# ProPrj___2025-10-14.net
KiCad netlist of a schematic drawn in EasyEDA Pro
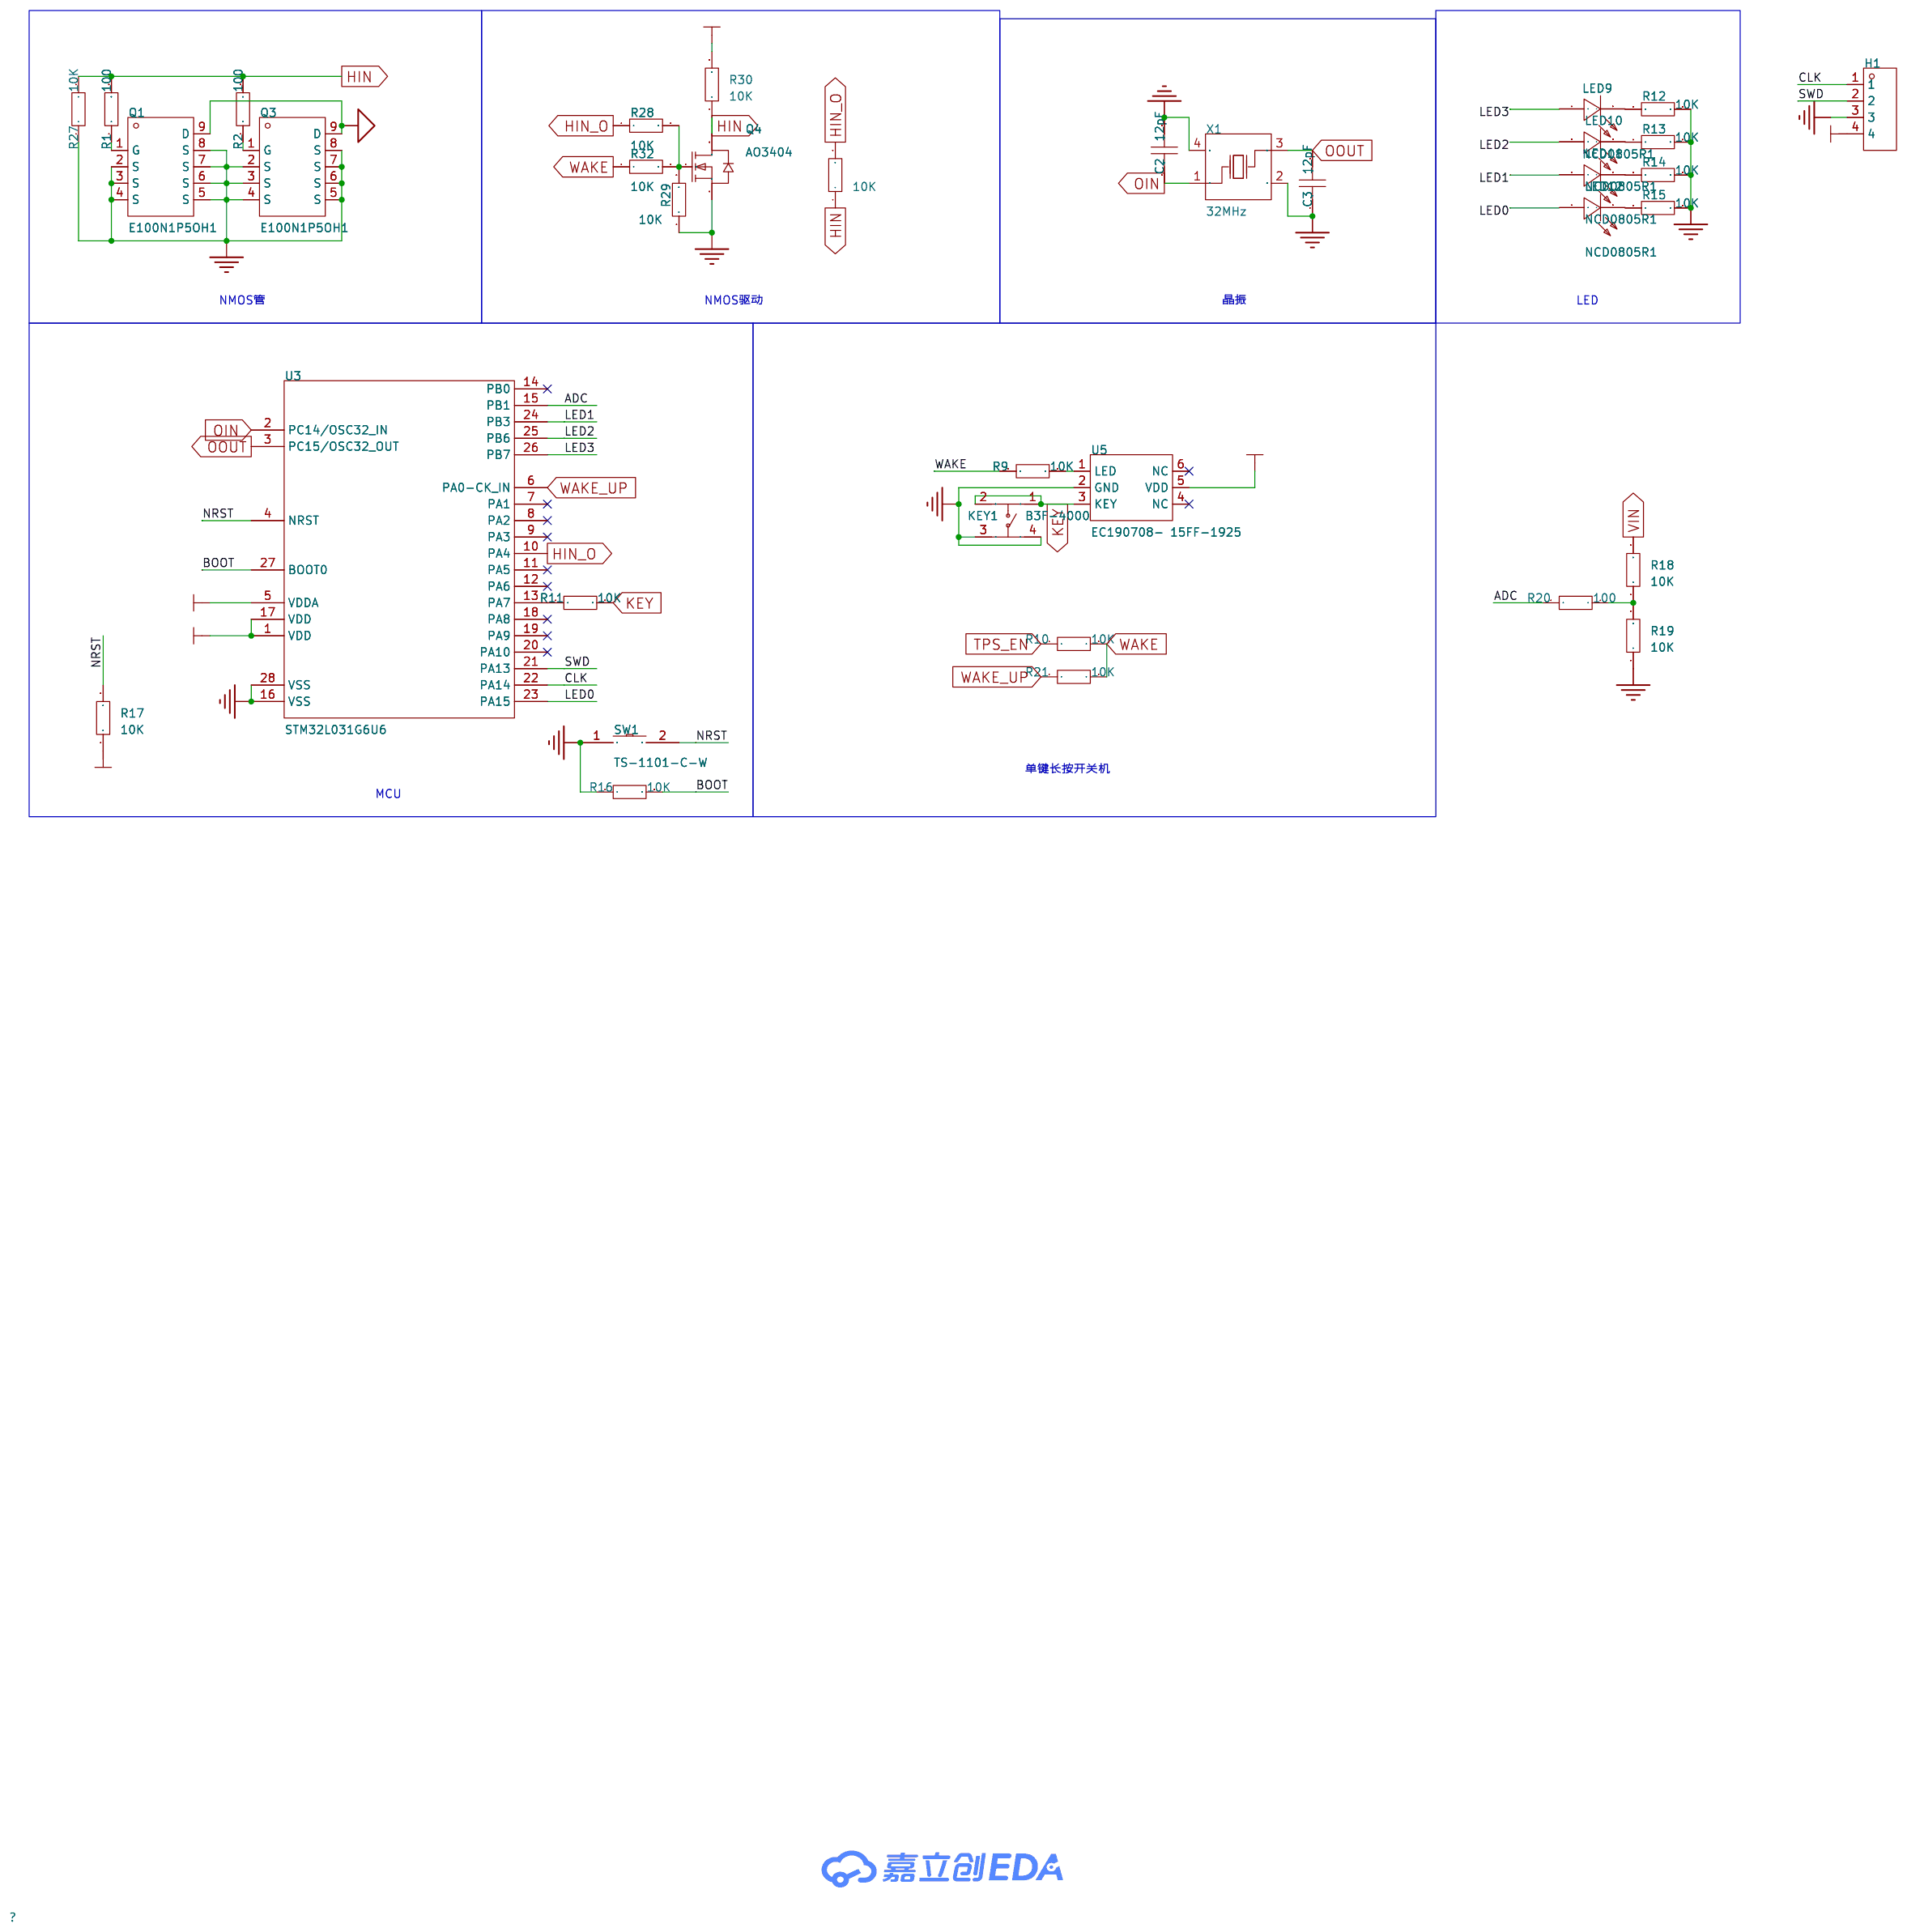
[diagram p0: P1]
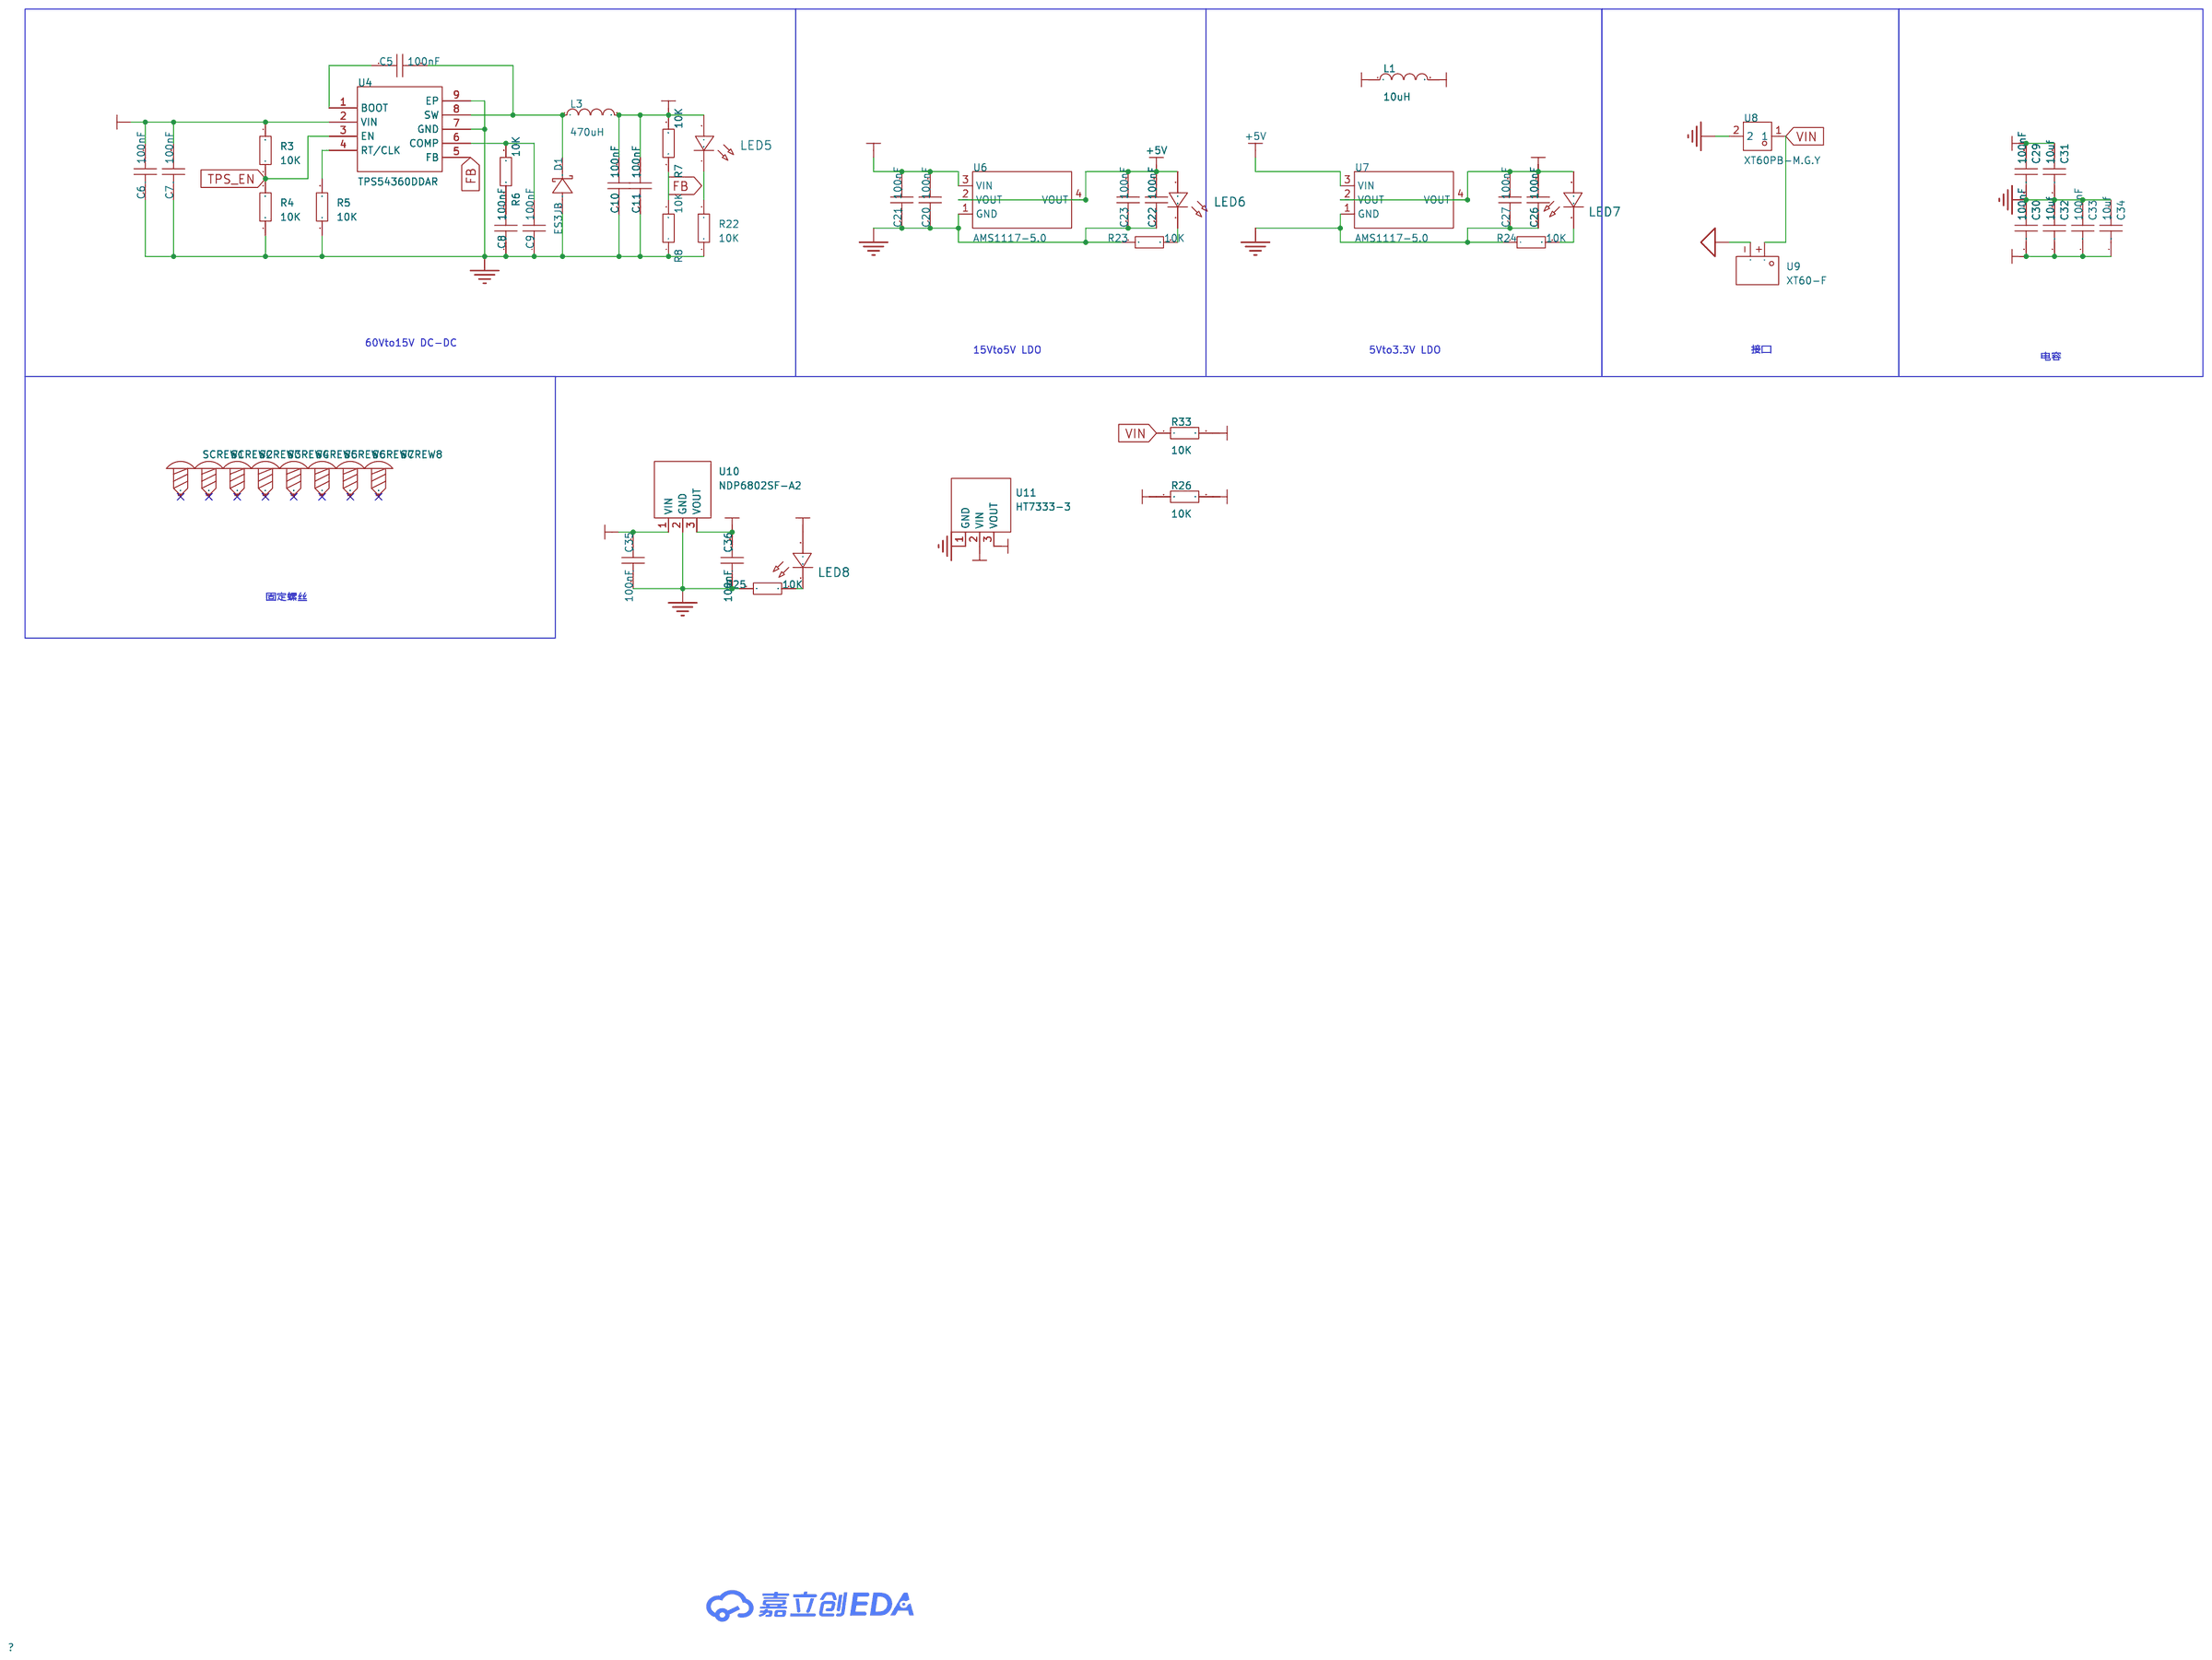
[diagram p1: PWOER]

(export (version "E")
  (design (tool "Eeschema 10.0.6"))
  (components
    (comp (ref "C2")
      (value "12pF")
      (footprint "easyedapro:C1206")
      (libsource (lib "easyedapro") (part "CapAcitance"))
    )
    (comp (ref "C3")
      (value "12pF")
      (footprint "easyedapro:C1206")
      (libsource (lib "easyedapro") (part "CapAcitance"))
    )
    (comp (ref "H1")
      (value "~")
      (footprint "easyedapro:HDR-TH_4P-P2.54-V-F")
      (libsource (lib "easyedapro") (part "2.54-1*4P母"))
    )
    (comp (ref "KEY1")
      (value "B3F-4000")
      (footprint "easyedapro:KEY-TH_4P-L12.0-W12.0-P5.00-LS13.4-EH")
      (description "电路结构:单刀单掷;按钮形状:圆形按钮;安装方式:直插;开关长度:12mm;开关宽度:12mm;开关高度:4.3mm;触点电流:50mA;额定电压(DC):24V;带灯:-;机械寿命:-;")
      (fields (field (name "Manufacturer") "OMRON(欧姆龙)"))
      (libsource (lib "easyedapro") (part "B3F-4000"))
    )
    (comp (ref "LED9")
      (value "NCD0805R1")
      (footprint "easyedapro:LED0805-R-RD")
      (fields (field (name "Manufacturer") "国星光电"))
      (libsource (lib "easyedapro") (part "FC-2012HRK-620D"))
    )
    (comp (ref "LED10")
      (value "NCD0805R1")
      (footprint "easyedapro:LED0805-R-RD")
      (fields (field (name "Manufacturer") "国星光电"))
      (libsource (lib "easyedapro") (part "FC-2012HRK-620D"))
    )
    (comp (ref "LED11")
      (value "NCD0805R1")
      (footprint "easyedapro:LED0805-R-RD")
      (fields (field (name "Manufacturer") "国星光电"))
      (libsource (lib "easyedapro") (part "FC-2012HRK-620D"))
    )
    (comp (ref "LED12")
      (value "NCD0805R1")
      (footprint "easyedapro:LED0805-R-RD")
      (fields (field (name "Manufacturer") "国星光电"))
      (libsource (lib "easyedapro") (part "FC-2012HRK-620D"))
    )
    (comp (ref "Q1")
      (value "E100N1P5OH1")
      (footprint "easyedapro:TOLL-8_L10.4-W9.9-P1.20-LS11.7-BL")
      (fields (field (name "Manufacturer") "Existar(毅芯达)"))
      (libsource (lib "easyedapro") (part "E100N1P5OH1"))
    )
    (comp (ref "Q3")
      (value "E100N1P5OH1")
      (footprint "easyedapro:TOLL-8_L10.4-W9.9-P1.20-LS11.7-BL")
      (fields (field (name "Manufacturer") "Existar(毅芯达)"))
      (libsource (lib "easyedapro") (part "E100N1P5OH1"))
    )
    (comp (ref "Q4")
      (value "AO3404")
      (footprint "easyedapro:SOT-23-3_L2.9-W1.3-P1.90-LS2.4-BR")
      (fields (field (name "Manufacturer") "Hottech(合科泰)"))
      (libsource (lib "easyedapro") (part "AO3404"))
    )
    (comp (ref "R1") (value "100") (footprint "easyedapro:R0603") (libsource (lib "easyedapro") (part "电阻")))
    (comp (ref "R2") (value "100") (footprint "easyedapro:R0603") (libsource (lib "easyedapro") (part "电阻")))
    (comp (ref "R9") (value "10K") (footprint "easyedapro:R0603") (libsource (lib "easyedapro") (part "电阻")))
    (comp (ref "R10") (value "10K") (footprint "easyedapro:R0603") (libsource (lib "easyedapro") (part "电阻")))
    (comp (ref "R11") (value "10K") (footprint "easyedapro:R0603") (libsource (lib "easyedapro") (part "电阻")))
    (comp (ref "R12") (value "10K") (footprint "easyedapro:R0603") (libsource (lib "easyedapro") (part "电阻")))
    (comp (ref "R13") (value "10K") (footprint "easyedapro:R0603") (libsource (lib "easyedapro") (part "电阻")))
    (comp (ref "R14") (value "10K") (footprint "easyedapro:R0603") (libsource (lib "easyedapro") (part "电阻")))
    (comp (ref "R15") (value "10K") (footprint "easyedapro:R0603") (libsource (lib "easyedapro") (part "电阻")))
    (comp (ref "R16") (value "10K") (footprint "easyedapro:R0603") (libsource (lib "easyedapro") (part "电阻")))
    (comp (ref "R17") (value "10K") (footprint "easyedapro:R0603") (libsource (lib "easyedapro") (part "电阻")))
    (comp (ref "R18") (value "10K") (footprint "easyedapro:R0603") (libsource (lib "easyedapro") (part "电阻")))
    (comp (ref "R19") (value "10K") (footprint "easyedapro:R0603") (libsource (lib "easyedapro") (part "电阻")))
    (comp (ref "R20") (value "100") (footprint "easyedapro:R0603") (libsource (lib "easyedapro") (part "电阻")))
    (comp (ref "R21") (value "10K") (footprint "easyedapro:R0603") (libsource (lib "easyedapro") (part "电阻")))
    (comp (ref "R27") (value "10K") (footprint "easyedapro:R0603") (libsource (lib "easyedapro") (part "电阻")))
    (comp (ref "R28") (value "10K") (footprint "easyedapro:R0603") (libsource (lib "easyedapro") (part "电阻")))
    (comp (ref "R29") (value "10K") (footprint "easyedapro:R0603") (libsource (lib "easyedapro") (part "电阻")))
    (comp (ref "R30") (value "10K") (footprint "easyedapro:R0603") (libsource (lib "easyedapro") (part "电阻")))
    (comp (ref "R31") (value "10K") (footprint "easyedapro:R0603") (libsource (lib "easyedapro") (part "电阻")))
    (comp (ref "R32") (value "10K") (footprint "easyedapro:R0603") (libsource (lib "easyedapro") (part "电阻")))
    (comp (ref "SW1")
      (value "TS-1101-C-W")
      (footprint "easyedapro:SW-SMD_L6.0-W3.3-LS8.0")
      (fields (field (name "Manufacturer") "XKB Connectivity(中国星坤)"))
      (libsource (lib "easyedapro") (part "TS-1101-C-W"))
    )
    (comp (ref "U3")
      (value "STM32L031G6U6")
      (footprint "easyedapro:UFQFPN-28_L4.0-W4.0-P0.50-BL")
      (description "CPU内核:ARM-M系列;应用领域:-;")
      (fields (field (name "Manufacturer") "ST(意法半导体)"))
      (libsource (lib "easyedapro") (part "STM32L031G6U6"))
    )
    (comp (ref "U5")
      (value "EC190708- 15FF-1925")
      (footprint "easyedapro:SOT-23-6_L2.9-W1.6-P0.95-LS2.9-BL")
      (libsource (lib "easyedapro") (part "EC190708- 15FF-1925"))
    )
    (comp (ref "X1")
      (value "32MHz")
      (footprint "easyedapro:CRYSTAL-SMD_4P-L3.2-W2.5-BL")
      (description "晶振类型:贴片晶振;频率:32MHz;常温频差:±10ppm;负载电容:12pF;频率稳定度:±20ppm;")
      (fields (field (name "Manufacturer Part") "X322532MOB4SI") (field (name "Manufacturer") "YXC(扬兴晶振)"))
      (libsource (lib "easyedapro") (part "X322532MOB4SI"))
    )
    (comp (ref "C5")
      (value "100nF")
      (footprint "easyedapro:C0805")
      (libsource (lib "easyedapro") (part "Capacitance"))
    )
    (comp (ref "C6")
      (value "100nF")
      (footprint "easyedapro:C1206")
      (libsource (lib "easyedapro") (part "CapAcitance"))
    )
    (comp (ref "C7")
      (value "100nF")
      (footprint "easyedapro:C1206")
      (libsource (lib "easyedapro") (part "CapAcitance"))
    )
    (comp (ref "C8")
      (value "100nF")
      (footprint "easyedapro:C0805")
      (libsource (lib "easyedapro") (part "Capacitance"))
    )
    (comp (ref "C9")
      (value "100nF")
      (footprint "easyedapro:C0805")
      (libsource (lib "easyedapro") (part "Capacitance"))
    )
    (comp (ref "C10")
      (value "100nF")
      (footprint "easyedapro:C1206")
      (libsource (lib "easyedapro") (part "CapAcitance"))
    )
    (comp (ref "C11")
      (value "100nF")
      (footprint "easyedapro:C1206")
      (libsource (lib "easyedapro") (part "CapAcitance"))
    )
    (comp (ref "C20")
      (value "100nF")
      (footprint "easyedapro:C0805")
      (libsource (lib "easyedapro") (part "Capacitance"))
    )
    (comp (ref "C21")
      (value "100nF")
      (footprint "easyedapro:C0805")
      (libsource (lib "easyedapro") (part "Capacitance"))
    )
    (comp (ref "C22")
      (value "100nF")
      (footprint "easyedapro:C0805")
      (libsource (lib "easyedapro") (part "Capacitance"))
    )
    (comp (ref "C23")
      (value "100nF")
      (footprint "easyedapro:C0805")
      (libsource (lib "easyedapro") (part "Capacitance"))
    )
    (comp (ref "C26")
      (value "100nF")
      (footprint "easyedapro:C0805")
      (libsource (lib "easyedapro") (part "Capacitance"))
    )
    (comp (ref "C27")
      (value "100nF")
      (footprint "easyedapro:C0805")
      (libsource (lib "easyedapro") (part "Capacitance"))
    )
    (comp (ref "C29")
      (value "100nF")
      (footprint "easyedapro:C1206")
      (libsource (lib "easyedapro") (part "CapAcitance"))
    )
    (comp (ref "C30")
      (value "100nF")
      (footprint "easyedapro:C1206")
      (libsource (lib "easyedapro") (part "CapAcitance"))
    )
    (comp (ref "C31")
      (value "10uf")
      (footprint "easyedapro:C1206")
      (libsource (lib "easyedapro") (part "CapAcitance"))
    )
    (comp (ref "C32")
      (value "10uf")
      (footprint "easyedapro:C1206")
      (libsource (lib "easyedapro") (part "CapAcitance"))
    )
    (comp (ref "C33")
      (value "100nF")
      (footprint "easyedapro:C1206")
      (libsource (lib "easyedapro") (part "CapAcitance"))
    )
    (comp (ref "C34")
      (value "10uf")
      (footprint "easyedapro:C1206")
      (libsource (lib "easyedapro") (part "CapAcitance"))
    )
    (comp (ref "C35")
      (value "100nF")
      (footprint "easyedapro:C1206")
      (libsource (lib "easyedapro") (part "CapAcitance"))
    )
    (comp (ref "C36")
      (value "100nF")
      (footprint "easyedapro:C1206")
      (libsource (lib "easyedapro") (part "CapAcitance"))
    )
    (comp (ref "D1")
      (value "ES3JB")
      (footprint "easyedapro:SMB_L4.6-W3.6-LS5.3-RD")
      (description "二极管配置:独立式;正向压降(Vf):1.7V@3A;直流反向耐压(Vr):600V;整流电流:3A;反向恢复时间(Trr):35ns;")
      (fields (field (name "Manufacturer") "R+O(宏嘉诚)"))
      (libsource (lib "easyedapro") (part "ES3JB_C18199163"))
    )
    (comp (ref "L1")
      (value "10uH")
      (footprint "easyedapro:L0805")
      (description "电感值:10uH;精度:±20%;额定电流:500mA;饱和电流(Isat):-;直流电阻(DCR):320mΩ;")
      (fields
        (field (name "Manufacturer Part") "MGFL2012F100MT-LF")
        (field (name "Manufacturer") "microgate(麦捷科技)")
      )
      (libsource (lib "easyedapro") (part "MGFL2012F100MT-LF"))
    )
    (comp (ref "L3")
      (value "470uH")
      (footprint "easyedapro:IND-SMD_L10.4-W10.3")
      (description "电感值:470uH;精度:±20%;额定电流:-;饱和电流(Isat):650mA;类型:磁胶屏蔽电感;")
      (fields (field (name "Manufacturer Part") "SMDRH104R-471MT") (field (name "Manufacturer") "SXN(顺翔诺)"))
      (libsource (lib "easyedapro") (part "SMDRH104R-471MT"))
    )
    (comp (ref "LED5")
      (value "~")
      (footprint "easyedapro:LED_0603")
      (libsource (lib "easyedapro") (part "LED_R"))
    )
    (comp (ref "LED6")
      (value "~")
      (footprint "easyedapro:LED_0603")
      (libsource (lib "easyedapro") (part "LED_R"))
    )
    (comp (ref "LED7")
      (value "~")
      (footprint "easyedapro:LED_0603")
      (libsource (lib "easyedapro") (part "LED_R"))
    )
    (comp (ref "LED8")
      (value "~")
      (footprint "easyedapro:LED_0603")
      (libsource (lib "easyedapro") (part "LED_R"))
    )
    (comp (ref "R3") (value "10K") (footprint "easyedapro:R0603") (libsource (lib "easyedapro") (part "电阻")))
    (comp (ref "R4") (value "10K") (footprint "easyedapro:R0603") (libsource (lib "easyedapro") (part "电阻")))
    (comp (ref "R5") (value "10K") (footprint "easyedapro:R0603") (libsource (lib "easyedapro") (part "电阻")))
    (comp (ref "R6") (value "10K") (footprint "easyedapro:R0603") (libsource (lib "easyedapro") (part "电阻")))
    (comp (ref "R7") (value "10K") (footprint "easyedapro:R0603") (libsource (lib "easyedapro") (part "电阻")))
    (comp (ref "R8") (value "10K") (footprint "easyedapro:R0603") (libsource (lib "easyedapro") (part "电阻")))
    (comp (ref "R22") (value "10K") (footprint "easyedapro:R0603") (libsource (lib "easyedapro") (part "电阻")))
    (comp (ref "R23") (value "10K") (footprint "easyedapro:R0603") (libsource (lib "easyedapro") (part "电阻")))
    (comp (ref "R24") (value "10K") (footprint "easyedapro:R0603") (libsource (lib "easyedapro") (part "电阻")))
    (comp (ref "R25") (value "10K") (footprint "easyedapro:R0603") (libsource (lib "easyedapro") (part "电阻")))
    (comp (ref "R26") (value "10K") (footprint "easyedapro:R0603") (libsource (lib "easyedapro") (part "电阻")))
    (comp (ref "R33") (value "10K") (footprint "easyedapro:R0603") (libsource (lib "easyedapro") (part "电阻")))
    (comp (ref "SCREW1")
      (value "~")
      (footprint "easyedapro:M3螺丝")
      (libsource (lib "easyedapro") (part "螺丝孔"))
    )
    (comp (ref "SCREW2")
      (value "~")
      (footprint "easyedapro:M3螺丝")
      (libsource (lib "easyedapro") (part "螺丝孔"))
    )
    (comp (ref "SCREW3")
      (value "~")
      (footprint "easyedapro:M3螺丝")
      (libsource (lib "easyedapro") (part "螺丝孔"))
    )
    (comp (ref "SCREW4")
      (value "~")
      (footprint "easyedapro:M3螺丝")
      (libsource (lib "easyedapro") (part "螺丝孔"))
    )
    (comp (ref "SCREW5")
      (value "~")
      (footprint "easyedapro:M3螺丝")
      (libsource (lib "easyedapro") (part "螺丝孔"))
    )
    (comp (ref "SCREW6")
      (value "~")
      (footprint "easyedapro:M3螺丝")
      (libsource (lib "easyedapro") (part "螺丝孔"))
    )
    (comp (ref "SCREW7")
      (value "~")
      (footprint "easyedapro:M3螺丝")
      (libsource (lib "easyedapro") (part "螺丝孔"))
    )
    (comp (ref "SCREW8")
      (value "~")
      (footprint "easyedapro:M3螺丝")
      (libsource (lib "easyedapro") (part "螺丝孔"))
    )
    (comp (ref "U4")
      (value "TPS54360DDAR")
      (footprint "easyedapro:SOIC-8_L5.0-W4.0-P1.27-LS6.0-BL-EP2.0")
      (description "功能类型:降压型;输出类型:可调;工作电压:4.5V~60V;输出电压:800mV~58.8V;输出电流:3.5A;")
      (fields (field (name "Manufacturer") "TI(德州仪器)"))
      (libsource (lib "easyedapro") (part "TPS54360DDAR"))
    )
    (comp (ref "U6")
      (value "AMS1117-5.0")
      (footprint "easyedapro:SOT-223_L6.5-W3.5-P2.30-LS7.0-BR")
      (description "输出类型:固定;工作电压:15V;输出电压:5V;输出电流:1A;电源纹波抑制比(PSRR):60dB;输出极性:正极;")
      (fields (field (name "Manufacturer") "AMS"))
      (libsource (lib "easyedapro") (part "AMS1117-5.0"))
    )
    (comp (ref "U7")
      (value "AMS1117-5.0")
      (footprint "easyedapro:SOT-223_L6.5-W3.5-P2.30-LS7.0-BR")
      (description "输出类型:固定;工作电压:15V;输出电压:5V;输出电流:1A;电源纹波抑制比(PSRR):60dB;输出极性:正极;")
      (fields (field (name "Manufacturer") "AMS"))
      (libsource (lib "easyedapro") (part "AMS1117-5.0"))
    )
    (comp (ref "U8")
      (value "XT60PB-M.G.Y")
      (footprint "easyedapro:CONN-TH_XT60PB-M")
      (fields (field (name "Manufacturer") "AMASS(艾迈斯)"))
      (libsource (lib "easyedapro") (part "XT60PB-M.G.Y"))
    )
    (comp (ref "U9")
      (value "XT60-F")
      (footprint "easyedapro:CONN-TH_XT60PB-F")
      (description "类别:-;类型1:-;")
      (fields (field (name "Manufacturer") "AMASS(艾迈斯)"))
      (libsource (lib "easyedapro") (part "XT60-F"))
    )
    (comp (ref "U10")
      (value "NDP6802SF-A2")
      (footprint "easyedapro:SOT-89-3_L4.5-W2.4-P1.50-LS4.0-BR")
      (description "输出类型:固定;工作电压:72V;输出电压:12V;输出电流:100mA;电源纹波抑制比(PSRR):60dB@(100Hz);输出极性:正极;")
      (fields (field (name "Manufacturer") "NDP(芯潭微)"))
      (libsource (lib "easyedapro") (part "NDP6802SF-A2"))
    )
    (comp (ref "U11")
      (value "HT7333-3")
      (footprint "easyedapro:SOT-89-3_L4.5-W2.5-P1.50-LS4.2-BR")
      (description "输出类型:固定;工作电压:30V;输出电压:3.3V;输出电流:250mA;电源纹波抑制比(PSRR):-;输出极性:正极;")
      (fields (field (name "Manufacturer") "HOLTEK(合泰/盛群)"))
      (libsource (lib "easyedapro") (part "HT7333-3"))
    )
  )
  (nets
    (net (code "1") (name "+5V") (class "Default")
      (node (ref "C22") (pin "2") (pinfunction "2_2") (pintype "input"))
      (node (ref "C23") (pin "2") (pinfunction "2_2") (pintype "input"))
      (node (ref "LED6") (pin "2") (pinfunction "A_2") (pintype "input"))
      (node (ref "U6") (pin "2") (pinfunction "VOUT_2") (pintype "unspecified"))
      (node (ref "U6") (pin "4") (pinfunction "VOUT_4") (pintype "unspecified"))
      (node (ref "U7") (pin "3") (pinfunction "VIN_3") (pintype "unspecified"))
    )
    (net (code "2") (name "+15V") (class "Default")
      (node (ref "C10") (pin "2") (pinfunction "2_2") (pintype "input"))
      (node (ref "C11") (pin "2") (pinfunction "2_2") (pintype "input"))
      (node (ref "C20") (pin "2") (pinfunction "2_2") (pintype "input"))
      (node (ref "C21") (pin "2") (pinfunction "2_2") (pintype "input"))
      (node (ref "L3") (pin "2") (pinfunction "2_2") (pintype "unspecified"))
      (node (ref "LED5") (pin "2") (pinfunction "A_2") (pintype "input"))
      (node (ref "R30") (pin "2") (pinfunction "2_2") (pintype "input"))
      (node (ref "R7") (pin "2") (pinfunction "2_2") (pintype "input"))
      (node (ref "U6") (pin "3") (pinfunction "VIN_3") (pintype "unspecified"))
    )
    (net (code "3") (name "3V3") (class "Default")
      (node (ref "C26") (pin "2") (pinfunction "2_2") (pintype "input"))
      (node (ref "C27") (pin "2") (pinfunction "2_2") (pintype "input"))
      (node (ref "C30") (pin "1") (pinfunction "1_1") (pintype "input"))
      (node (ref "C32") (pin "1") (pinfunction "1_1") (pintype "input"))
      (node (ref "C33") (pin "1") (pinfunction "1_1") (pintype "input"))
      (node (ref "C34") (pin "1") (pinfunction "1_1") (pintype "input"))
      (node (ref "H1") (pin "4") (pinfunction "4_4") (pintype "unspecified"))
      (node (ref "L1") (pin "2") (pinfunction "2_2") (pintype "unspecified"))
      (node (ref "LED7") (pin "2") (pinfunction "A_2") (pintype "input"))
      (node (ref "R17") (pin "1") (pinfunction "1_1") (pintype "input"))
      (node (ref "R26") (pin "2") (pinfunction "2_2") (pintype "input"))
      (node (ref "U3") (pin "1") (pinfunction "VDD_1") (pintype "input"))
      (node (ref "U3") (pin "17") (pinfunction "VDD_17") (pintype "bidirectional"))
      (node (ref "U7") (pin "2") (pinfunction "VOUT_2") (pintype "unspecified"))
      (node (ref "U7") (pin "4") (pinfunction "VOUT_4") (pintype "unspecified"))
    )
    (net (code "4") (name "3V3A") (class "Default")
      (node (ref "C29") (pin "2") (pinfunction "2_2") (pintype "input"))
      (node (ref "C31") (pin "2") (pinfunction "2_2") (pintype "input"))
      (node (ref "L1") (pin "1") (pinfunction "1_1") (pintype "unspecified"))
      (node (ref "U3") (pin "5") (pinfunction "VDDA_5") (pintype "bidirectional"))
    )
    (net (code "5") (name "3V32") (class "Default")
      (node (ref "LED8") (pin "2") (pinfunction "A_2") (pintype "input"))
      (node (ref "R26") (pin "1") (pinfunction "1_1") (pintype "input"))
      (node (ref "U11") (pin "3") (pinfunction "VOUT_3") (pintype "unspecified"))
      (node (ref "U5") (pin "5") (pinfunction "VDD_5") (pintype "unspecified"))
    )
    (net (code "6") (name "12V") (class "Default")
      (node (ref "C36") (pin "2") (pinfunction "2_2") (pintype "input"))
      (node (ref "U10") (pin "3") (pinfunction "VOUT_3") (pintype "unspecified"))
      (node (ref "U11") (pin "2") (pinfunction "VIN_2") (pintype "unspecified"))
    )
    (net (code "7") (name "ADC") (class "Default")
      (node (ref "R20") (pin "2") (pinfunction "2_2") (pintype "input"))
      (node (ref "U3") (pin "15") (pinfunction "PB1_15") (pintype "bidirectional"))
    )
    (net (code "8") (name "AGND") (class "Default")
      (node (ref "Q1") (pin "9") (pinfunction "D_9") (pintype "unspecified"))
      (node (ref "Q3") (pin "9") (pinfunction "D_9") (pintype "unspecified"))
      (node (ref "U9") (pin "-") (pinfunction "2_-") (pintype "unspecified"))
    )
    (net (code "9") (name "BOOT") (class "Default")
      (node (ref "R16") (pin "2") (pinfunction "2_2") (pintype "input"))
      (node (ref "U3") (pin "27") (pinfunction "BOOT0_27") (pintype "bidirectional"))
    )
    (net (code "10") (name "CLK") (class "Default")
      (node (ref "H1") (pin "1") (pinfunction "1_1") (pintype "unspecified"))
      (node (ref "U3") (pin "22") (pinfunction "PA14_22") (pintype "bidirectional"))
    )
    (net (code "11") (name "FB") (class "Default")
      (node (ref "R7") (pin "1") (pinfunction "1_1") (pintype "input"))
      (node (ref "R8") (pin "2") (pinfunction "2_2") (pintype "input"))
      (node (ref "U4") (pin "5") (pinfunction "FB_5") (pintype "unspecified"))
    )
    (net (code "12") (name "GND") (class "Default")
      (node (ref "C10") (pin "1") (pinfunction "1_1") (pintype "input"))
      (node (ref "C11") (pin "1") (pinfunction "1_1") (pintype "input"))
      (node (ref "C2") (pin "2") (pinfunction "2_2") (pintype "input"))
      (node (ref "C20") (pin "1") (pinfunction "1_1") (pintype "input"))
      (node (ref "C21") (pin "1") (pinfunction "1_1") (pintype "input"))
      (node (ref "C22") (pin "1") (pinfunction "1_1") (pintype "input"))
      (node (ref "C23") (pin "1") (pinfunction "1_1") (pintype "input"))
      (node (ref "C26") (pin "1") (pinfunction "1_1") (pintype "input"))
      (node (ref "C27") (pin "1") (pinfunction "1_1") (pintype "input"))
      (node (ref "C29") (pin "1") (pinfunction "1_1") (pintype "input"))
      (node (ref "C3") (pin "1") (pinfunction "1_1") (pintype "input"))
      (node (ref "C30") (pin "2") (pinfunction "2_2") (pintype "input"))
      (node (ref "C31") (pin "1") (pinfunction "1_1") (pintype "input"))
      (node (ref "C32") (pin "2") (pinfunction "2_2") (pintype "input"))
      (node (ref "C33") (pin "2") (pinfunction "2_2") (pintype "input"))
      (node (ref "C34") (pin "2") (pinfunction "2_2") (pintype "input"))
      (node (ref "C35") (pin "2") (pinfunction "2_2") (pintype "input"))
      (node (ref "C36") (pin "1") (pinfunction "1_1") (pintype "input"))
      (node (ref "C6") (pin "1") (pinfunction "1_1") (pintype "input"))
      (node (ref "C7") (pin "1") (pinfunction "1_1") (pintype "input"))
      (node (ref "C8") (pin "1") (pinfunction "1_1") (pintype "input"))
      (node (ref "C9") (pin "1") (pinfunction "1_1") (pintype "input"))
      (node (ref "D1") (pin "2") (pinfunction "A_2") (pintype "unspecified"))
      (node (ref "H1") (pin "3") (pinfunction "3_3") (pintype "unspecified"))
      (node (ref "KEY1") (pin "3") (pinfunction "3_3") (pintype "unspecified"))
      (node (ref "KEY1") (pin "4") (pinfunction "4_4") (pintype "unspecified"))
      (node (ref "Q1") (pin "2") (pinfunction "S_2") (pintype "unspecified"))
      (node (ref "Q1") (pin "3") (pinfunction "S_3") (pintype "unspecified"))
      (node (ref "Q1") (pin "4") (pinfunction "S_4") (pintype "unspecified"))
      (node (ref "Q1") (pin "5") (pinfunction "S_5") (pintype "unspecified"))
      (node (ref "Q1") (pin "6") (pinfunction "S_6") (pintype "unspecified"))
      (node (ref "Q1") (pin "7") (pinfunction "S_7") (pintype "unspecified"))
      (node (ref "Q1") (pin "8") (pinfunction "S_8") (pintype "unspecified"))
      (node (ref "Q3") (pin "2") (pinfunction "S_2") (pintype "unspecified"))
      (node (ref "Q3") (pin "3") (pinfunction "S_3") (pintype "unspecified"))
      (node (ref "Q3") (pin "4") (pinfunction "S_4") (pintype "unspecified"))
      (node (ref "Q3") (pin "5") (pinfunction "S_5") (pintype "unspecified"))
      (node (ref "Q3") (pin "6") (pinfunction "S_6") (pintype "unspecified"))
      (node (ref "Q3") (pin "7") (pinfunction "S_7") (pintype "unspecified"))
      (node (ref "Q3") (pin "8") (pinfunction "S_8") (pintype "unspecified"))
      (node (ref "Q4") (pin "2") (pinfunction "S_2") (pintype "unspecified"))
      (node (ref "R12") (pin "2") (pinfunction "2_2") (pintype "input"))
      (node (ref "R13") (pin "2") (pinfunction "2_2") (pintype "input"))
      (node (ref "R14") (pin "2") (pinfunction "2_2") (pintype "input"))
      (node (ref "R15") (pin "2") (pinfunction "2_2") (pintype "input"))
      (node (ref "R16") (pin "1") (pinfunction "1_1") (pintype "input"))
      (node (ref "R19") (pin "1") (pinfunction "1_1") (pintype "input"))
      (node (ref "R22") (pin "1") (pinfunction "1_1") (pintype "input"))
      (node (ref "R23") (pin "1") (pinfunction "1_1") (pintype "input"))
      (node (ref "R24") (pin "1") (pinfunction "1_1") (pintype "input"))
      (node (ref "R25") (pin "1") (pinfunction "1_1") (pintype "input"))
      (node (ref "R27") (pin "1") (pinfunction "1_1") (pintype "input"))
      (node (ref "R29") (pin "1") (pinfunction "1_1") (pintype "input"))
      (node (ref "R4") (pin "1") (pinfunction "1_1") (pintype "input"))
      (node (ref "R5") (pin "1") (pinfunction "1_1") (pintype "input"))
      (node (ref "R8") (pin "1") (pinfunction "1_1") (pintype "input"))
      (node (ref "SW1") (pin "1") (pinfunction "1_1") (pintype "unspecified"))
      (node (ref "U10") (pin "2") (pinfunction "GND_2") (pintype "unspecified"))
      (node (ref "U11") (pin "1") (pinfunction "GND_1") (pintype "unspecified"))
      (node (ref "U3") (pin "16") (pinfunction "VSS_16") (pintype "bidirectional"))
      (node (ref "U3") (pin "28") (pinfunction "VSS_28") (pintype "bidirectional"))
      (node (ref "U4") (pin "7") (pinfunction "GND_7") (pintype "unspecified"))
      (node (ref "U4") (pin "9") (pinfunction "EP_9") (pintype "unspecified"))
      (node (ref "U5") (pin "2") (pinfunction "GND_2") (pintype "unspecified"))
      (node (ref "U6") (pin "1") (pinfunction "GND_1") (pintype "unspecified"))
      (node (ref "U7") (pin "1") (pinfunction "GND_1") (pintype "unspecified"))
      (node (ref "U8") (pin "2") (pinfunction "2_2") (pintype "unspecified"))
      (node (ref "X1") (pin "2") (pinfunction "GND_2") (pintype "unspecified"))
      (node (ref "X1") (pin "4") (pinfunction "GND_4") (pintype "unspecified"))
    )
    (net (code "13") (name "HIN") (class "Default")
      (node (ref "Q4") (pin "3") (pinfunction "D_3") (pintype "unspecified"))
      (node (ref "R1") (pin "2") (pinfunction "2_2") (pintype "input"))
      (node (ref "R2") (pin "2") (pinfunction "2_2") (pintype "input"))
      (node (ref "R27") (pin "2") (pinfunction "2_2") (pintype "input"))
      (node (ref "R30") (pin "1") (pinfunction "1_1") (pintype "input"))
      (node (ref "R31") (pin "1") (pinfunction "1_1") (pintype "input"))
    )
    (net (code "14") (name "HIN_O") (class "Default")
      (node (ref "R28") (pin "1") (pinfunction "1_1") (pintype "input"))
      (node (ref "R31") (pin "2") (pinfunction "2_2") (pintype "input"))
      (node (ref "U3") (pin "10") (pinfunction "PA4_10") (pintype "bidirectional"))
    )
    (net (code "15") (name "KEY") (class "Default")
      (node (ref "KEY1") (pin "1") (pinfunction "1_1") (pintype "unspecified"))
      (node (ref "KEY1") (pin "2") (pinfunction "2_2") (pintype "unspecified"))
      (node (ref "R11") (pin "2") (pinfunction "2_2") (pintype "input"))
      (node (ref "U5") (pin "3") (pinfunction "KEY_3") (pintype "unspecified"))
    )
    (net (code "16") (name "LED0") (class "Default")
      (node (ref "U3") (pin "23") (pinfunction "PA15_23") (pintype "bidirectional"))
    )
    (net (code "17") (name "LED1") (class "Default")
      (node (ref "U3") (pin "24") (pinfunction "PB3_24") (pintype "bidirectional"))
    )
    (net (code "18") (name "LED2") (class "Default")
      (node (ref "U3") (pin "25") (pinfunction "PB6_25") (pintype "bidirectional"))
    )
    (net (code "19") (name "LED3") (class "Default")
      (node (ref "U3") (pin "26") (pinfunction "PB7_26") (pintype "bidirectional"))
    )
    (net (code "20") (name "NRST") (class "Default")
      (node (ref "R17") (pin "2") (pinfunction "2_2") (pintype "input"))
      (node (ref "SW1") (pin "2") (pinfunction "2_2") (pintype "unspecified"))
      (node (ref "U3") (pin "4") (pinfunction "NRST_4") (pintype "input"))
    )
    (net (code "21") (name "Net-(C8-Pad2)") (class "Default")
      (node (ref "C8") (pin "2") (pinfunction "2_2") (pintype "input"))
      (node (ref "R6") (pin "1") (pinfunction "1_1") (pintype "input"))
    )
    (net (code "22") (name "Net-(D1-K)") (class "Default")
      (node (ref "C5") (pin "2") (pinfunction "2_2") (pintype "input"))
      (node (ref "D1") (pin "1") (pinfunction "K_1") (pintype "unspecified"))
      (node (ref "L3") (pin "1") (pinfunction "1_1") (pintype "unspecified"))
      (node (ref "U4") (pin "8") (pinfunction "SW_8") (pintype "unspecified"))
    )
    (net (code "23") (name "Net-(LED5-C)") (class "Default")
      (node (ref "LED5") (pin "1") (pinfunction "C_1") (pintype "input"))
      (node (ref "R22") (pin "2") (pinfunction "2_2") (pintype "input"))
    )
    (net (code "24") (name "Net-(LED6-C)") (class "Default")
      (node (ref "LED6") (pin "1") (pinfunction "C_1") (pintype "input"))
      (node (ref "R23") (pin "2") (pinfunction "2_2") (pintype "input"))
    )
    (net (code "25") (name "Net-(LED7-C)") (class "Default")
      (node (ref "LED7") (pin "1") (pinfunction "C_1") (pintype "input"))
      (node (ref "R24") (pin "2") (pinfunction "2_2") (pintype "input"))
    )
    (net (code "26") (name "Net-(LED8-C)") (class "Default")
      (node (ref "LED8") (pin "1") (pinfunction "C_1") (pintype "input"))
      (node (ref "R25") (pin "2") (pinfunction "2_2") (pintype "input"))
    )
    (net (code "27") (name "Net-(Q1-G)") (class "Default")
      (node (ref "Q1") (pin "1") (pinfunction "G_1") (pintype "unspecified"))
      (node (ref "R1") (pin "1") (pinfunction "1_1") (pintype "input"))
    )
    (net (code "28") (name "Net-(Q3-G)") (class "Default")
      (node (ref "Q3") (pin "1") (pinfunction "G_1") (pintype "unspecified"))
      (node (ref "R2") (pin "1") (pinfunction "1_1") (pintype "input"))
    )
    (net (code "29") (name "Net-(Q4-G)") (class "Default")
      (node (ref "Q4") (pin "1") (pinfunction "G_1") (pintype "unspecified"))
      (node (ref "R28") (pin "2") (pinfunction "2_2") (pintype "input"))
      (node (ref "R29") (pin "2") (pinfunction "2_2") (pintype "input"))
      (node (ref "R32") (pin "2") (pinfunction "2_2") (pintype "input"))
    )
    (net (code "30") (name "Net-(R18-Pad1)") (class "Default")
      (node (ref "R18") (pin "1") (pinfunction "1_1") (pintype "input"))
      (node (ref "R19") (pin "2") (pinfunction "2_2") (pintype "input"))
      (node (ref "R20") (pin "1") (pinfunction "1_1") (pintype "input"))
    )
    (net (code "31") (name "Net-(U3-PA7)") (class "Default")
      (node (ref "R11") (pin "1") (pinfunction "1_1") (pintype "input"))
      (node (ref "U3") (pin "13") (pinfunction "PA7_13") (pintype "bidirectional"))
    )
    (net (code "32") (name "Net-(U4-BOOT)") (class "Default")
      (node (ref "C5") (pin "1") (pinfunction "1_1") (pintype "input"))
      (node (ref "U4") (pin "1") (pinfunction "BOOT_1") (pintype "unspecified"))
    )
    (net (code "33") (name "Net-(U4-COMP)") (class "Default")
      (node (ref "C9") (pin "2") (pinfunction "2_2") (pintype "input"))
      (node (ref "R6") (pin "2") (pinfunction "2_2") (pintype "input"))
      (node (ref "U4") (pin "6") (pinfunction "COMP_6") (pintype "unspecified"))
    )
    (net (code "34") (name "Net-(U4-RT{slash}CLK)") (class "Default")
      (node (ref "R5") (pin "2") (pinfunction "2_2") (pintype "input"))
      (node (ref "U4") (pin "4") (pinfunction "RT/CLK_4") (pintype "unspecified"))
    )
    (net (code "35") (name "Net-(U5-LED)") (class "Default")
      (node (ref "R9") (pin "2") (pinfunction "2_2") (pintype "input"))
      (node (ref "U5") (pin "1") (pinfunction "LED_1") (pintype "unspecified"))
    )
    (net (code "36") (name "OIN") (class "Default")
      (node (ref "C2") (pin "1") (pinfunction "1_1") (pintype "input"))
      (node (ref "U3") (pin "2") (pinfunction "PC14/OSC32_IN_2") (pintype "bidirectional"))
      (node (ref "X1") (pin "1") (pinfunction "OSC1_1") (pintype "unspecified"))
    )
    (net (code "37") (name "OOUT") (class "Default")
      (node (ref "C3") (pin "2") (pinfunction "2_2") (pintype "input"))
      (node (ref "U3") (pin "3") (pinfunction "PC15/OSC32_OUT_3") (pintype "bidirectional"))
      (node (ref "X1") (pin "3") (pinfunction "OSC2_3") (pintype "unspecified"))
    )
    (net (code "38") (name "SWD") (class "Default")
      (node (ref "H1") (pin "2") (pinfunction "2_2") (pintype "unspecified"))
      (node (ref "U3") (pin "21") (pinfunction "PA13_21") (pintype "bidirectional"))
    )
    (net (code "39") (name "TPS_EN") (class "Default")
      (node (ref "R10") (pin "1") (pinfunction "1_1") (pintype "input"))
      (node (ref "R3") (pin "1") (pinfunction "1_1") (pintype "input"))
      (node (ref "R4") (pin "2") (pinfunction "2_2") (pintype "input"))
      (node (ref "U4") (pin "3") (pinfunction "EN_3") (pintype "unspecified"))
    )
    (net (code "40") (name "VIN") (class "Default")
      (node (ref "R18") (pin "2") (pinfunction "2_2") (pintype "input"))
      (node (ref "R33") (pin "1") (pinfunction "1_1") (pintype "input"))
      (node (ref "U8") (pin "1") (pinfunction "1_1") (pintype "unspecified"))
      (node (ref "U9") (pin "+") (pinfunction "1_+") (pintype "unspecified"))
    )
    (net (code "41") (name "VIN_1") (class "Default")
      (node (ref "C35") (pin "1") (pinfunction "1_1") (pintype "input"))
      (node (ref "C6") (pin "2") (pinfunction "2_2") (pintype "input"))
      (node (ref "C7") (pin "2") (pinfunction "2_2") (pintype "input"))
      (node (ref "R3") (pin "2") (pinfunction "2_2") (pintype "input"))
      (node (ref "R33") (pin "2") (pinfunction "2_2") (pintype "input"))
      (node (ref "U10") (pin "1") (pinfunction "VIN_1") (pintype "unspecified"))
      (node (ref "U4") (pin "2") (pinfunction "VIN_2") (pintype "unspecified"))
    )
    (net (code "42") (name "WAKE") (class "Default")
      (node (ref "R10") (pin "2") (pinfunction "2_2") (pintype "input"))
      (node (ref "R21") (pin "2") (pinfunction "2_2") (pintype "input"))
      (node (ref "R32") (pin "1") (pinfunction "1_1") (pintype "input"))
      (node (ref "R9") (pin "1") (pinfunction "1_1") (pintype "input"))
    )
    (net (code "43") (name "WAKE_UP") (class "Default")
      (node (ref "R21") (pin "1") (pinfunction "1_1") (pintype "input"))
      (node (ref "U3") (pin "6") (pinfunction "PA0-CK_IN_6") (pintype "bidirectional"))
    )
    (net (code "44") (name "unconnected-(LED9-+-Pad1)") (class "Default")
      (node (ref "LED9") (pin "1") (pinfunction "+_1") (pintype "unspecified"))
    )
    (net (code "45") (name "unconnected-(LED9---Pad2)") (class "Default")
      (node (ref "LED9") (pin "2") (pinfunction "-_2") (pintype "unspecified"))
    )
    (net (code "46") (name "unconnected-(LED10-+-Pad1)") (class "Default")
      (node (ref "LED10") (pin "1") (pinfunction "+_1") (pintype "unspecified"))
    )
    (net (code "47") (name "unconnected-(LED10---Pad2)") (class "Default")
      (node (ref "LED10") (pin "2") (pinfunction "-_2") (pintype "unspecified"))
    )
    (net (code "48") (name "unconnected-(LED11-+-Pad1)") (class "Default")
      (node (ref "LED11") (pin "1") (pinfunction "+_1") (pintype "unspecified"))
    )
    (net (code "49") (name "unconnected-(LED11---Pad2)") (class "Default")
      (node (ref "LED11") (pin "2") (pinfunction "-_2") (pintype "unspecified"))
    )
    (net (code "50") (name "unconnected-(LED12-+-Pad1)") (class "Default")
      (node (ref "LED12") (pin "1") (pinfunction "+_1") (pintype "unspecified"))
    )
    (net (code "51") (name "unconnected-(LED12---Pad2)") (class "Default")
      (node (ref "LED12") (pin "2") (pinfunction "-_2") (pintype "unspecified"))
    )
    (net (code "52") (name "unconnected-(R12-Pad1)") (class "Default")
      (node (ref "R12") (pin "1") (pinfunction "1_1") (pintype "input"))
    )
    (net (code "53") (name "unconnected-(R13-Pad1)") (class "Default")
      (node (ref "R13") (pin "1") (pinfunction "1_1") (pintype "input"))
    )
    (net (code "54") (name "unconnected-(R14-Pad1)") (class "Default")
      (node (ref "R14") (pin "1") (pinfunction "1_1") (pintype "input"))
    )
    (net (code "55") (name "unconnected-(R15-Pad1)") (class "Default")
      (node (ref "R15") (pin "1") (pinfunction "1_1") (pintype "input"))
    )
    (net (code "56") (name "unconnected-(SCREW1-Pad1)") (class "Default")
      (node (ref "SCREW1") (pin "1") (pinfunction "1_1") (pintype "input+no_connect"))
    )
    (net (code "57") (name "unconnected-(SCREW2-Pad1)") (class "Default")
      (node (ref "SCREW2") (pin "1") (pinfunction "1_1") (pintype "input+no_connect"))
    )
    (net (code "58") (name "unconnected-(SCREW3-Pad1)") (class "Default")
      (node (ref "SCREW3") (pin "1") (pinfunction "1_1") (pintype "input+no_connect"))
    )
    (net (code "59") (name "unconnected-(SCREW4-Pad1)") (class "Default")
      (node (ref "SCREW4") (pin "1") (pinfunction "1_1") (pintype "input+no_connect"))
    )
    (net (code "60") (name "unconnected-(SCREW5-Pad1)") (class "Default")
      (node (ref "SCREW5") (pin "1") (pinfunction "1_1") (pintype "input+no_connect"))
    )
    (net (code "61") (name "unconnected-(SCREW6-Pad1)") (class "Default")
      (node (ref "SCREW6") (pin "1") (pinfunction "1_1") (pintype "input+no_connect"))
    )
    (net (code "62") (name "unconnected-(SCREW7-Pad1)") (class "Default")
      (node (ref "SCREW7") (pin "1") (pinfunction "1_1") (pintype "input+no_connect"))
    )
    (net (code "63") (name "unconnected-(SCREW8-Pad1)") (class "Default")
      (node (ref "SCREW8") (pin "1") (pinfunction "1_1") (pintype "input+no_connect"))
    )
    (net (code "64") (name "unconnected-(U3-PA1-Pad7)") (class "Default")
      (node (ref "U3") (pin "7") (pinfunction "PA1_7") (pintype "bidirectional+no_connect"))
    )
    (net (code "65") (name "unconnected-(U3-PA2-Pad8)") (class "Default")
      (node (ref "U3") (pin "8") (pinfunction "PA2_8") (pintype "bidirectional+no_connect"))
    )
    (net (code "66") (name "unconnected-(U3-PA3-Pad9)") (class "Default")
      (node (ref "U3") (pin "9") (pinfunction "PA3_9") (pintype "bidirectional+no_connect"))
    )
    (net (code "67") (name "unconnected-(U3-PA5-Pad11)") (class "Default")
      (node (ref "U3") (pin "11") (pinfunction "PA5_11") (pintype "bidirectional+no_connect"))
    )
    (net (code "68") (name "unconnected-(U3-PA6-Pad12)") (class "Default")
      (node (ref "U3") (pin "12") (pinfunction "PA6_12") (pintype "bidirectional+no_connect"))
    )
    (net (code "69") (name "unconnected-(U3-PA8-Pad18)") (class "Default")
      (node (ref "U3") (pin "18") (pinfunction "PA8_18") (pintype "bidirectional+no_connect"))
    )
    (net (code "70") (name "unconnected-(U3-PA9-Pad19)") (class "Default")
      (node (ref "U3") (pin "19") (pinfunction "PA9_19") (pintype "bidirectional+no_connect"))
    )
    (net (code "71") (name "unconnected-(U3-PA10-Pad20)") (class "Default")
      (node (ref "U3") (pin "20") (pinfunction "PA10_20") (pintype "bidirectional+no_connect"))
    )
    (net (code "72") (name "unconnected-(U3-PB0-Pad14)") (class "Default")
      (node (ref "U3") (pin "14") (pinfunction "PB0_14") (pintype "bidirectional+no_connect"))
    )
    (net (code "73") (name "unconnected-(U5-NC-Pad4)") (class "Default")
      (node (ref "U5") (pin "4") (pinfunction "NC_4") (pintype "unspecified+no_connect"))
    )
    (net (code "74") (name "unconnected-(U5-NC-Pad6)") (class "Default")
      (node (ref "U5") (pin "6") (pinfunction "NC_6") (pintype "unspecified+no_connect"))
    )
  )
)
